# e-Tapperhandpiece19.net
KiCad netlist of a schematic drawn in EAGLE
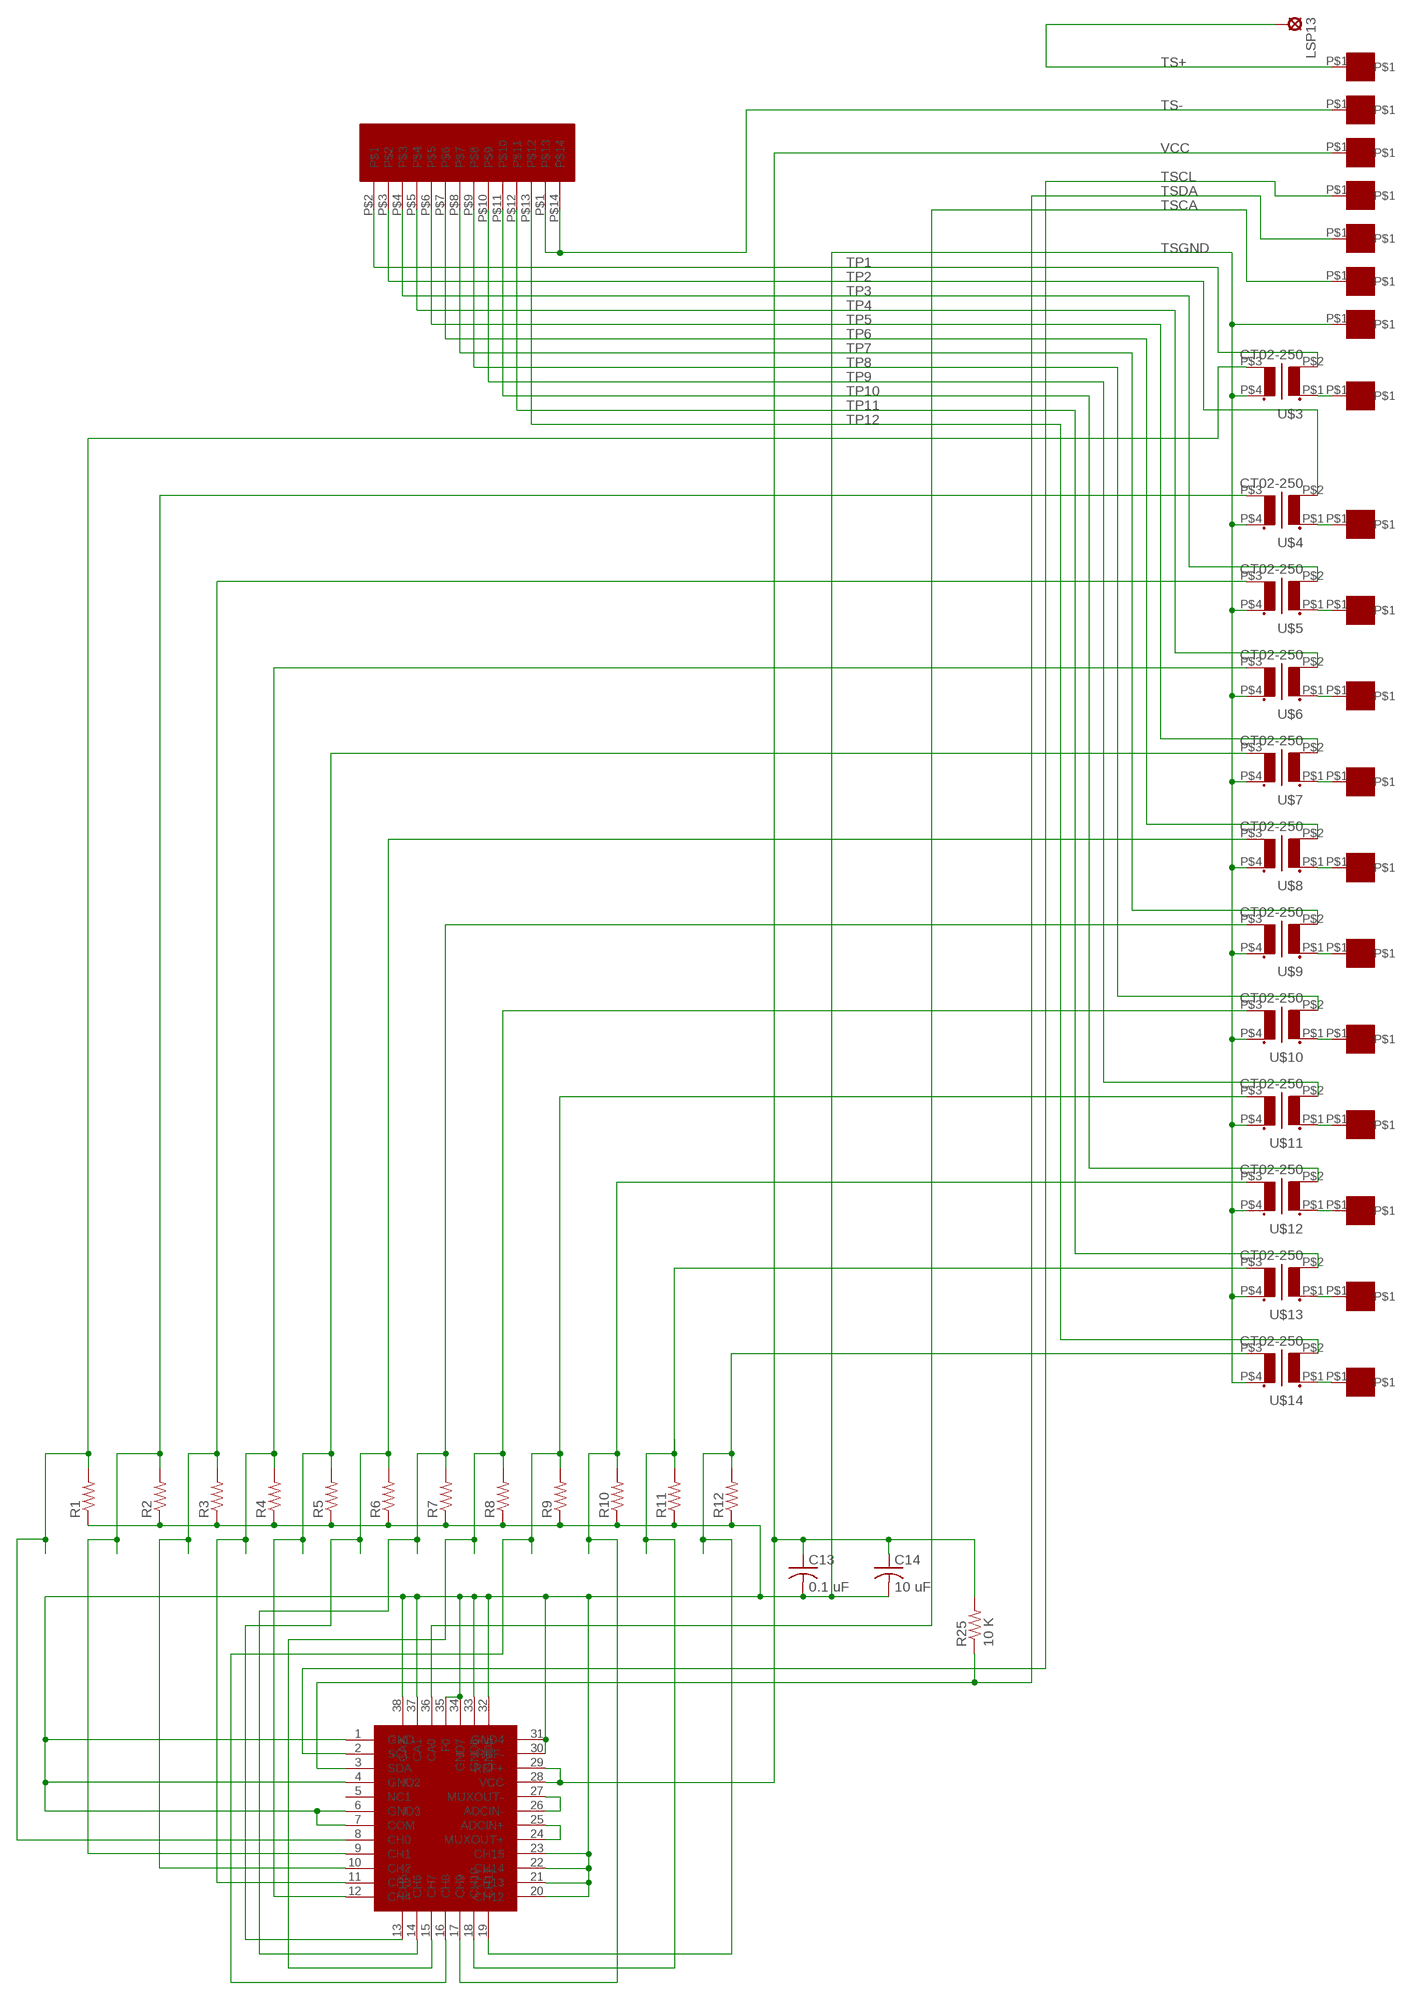
[diagram p0: schematic, sheet 1]

(export (version "E")
  (design (tool "Eeschema 10.0.6"))
  (components
    (comp (ref "C13")
      (value "0.1 uF")
      (footprint "eagle-import:C0603")
      (libsource (lib "eagle-import") (part "C-USC0603"))
    )
    (comp (ref "C14")
      (value "10 uF")
      (footprint "eagle-import:C0805")
      (libsource (lib "eagle-import") (part "C-USC0805"))
    )
    (comp (ref "LSP13")
      (value "SE11")
      (footprint "eagle-import:SE11")
      (libsource (lib "eagle-import") (part "SE11"))
    )
    (comp (ref "R1")
      (value "R-US_R0402")
      (footprint "eagle-import:R0402")
      (libsource (lib "eagle-import") (part "R-US_R0402"))
    )
    (comp (ref "R2")
      (value "R-US_R0402")
      (footprint "eagle-import:R0402")
      (libsource (lib "eagle-import") (part "R-US_R0402"))
    )
    (comp (ref "R3")
      (value "R-US_R0402")
      (footprint "eagle-import:R0402")
      (libsource (lib "eagle-import") (part "R-US_R0402"))
    )
    (comp (ref "R4")
      (value "R-US_R0402")
      (footprint "eagle-import:R0402")
      (libsource (lib "eagle-import") (part "R-US_R0402"))
    )
    (comp (ref "R5")
      (value "R-US_R0402")
      (footprint "eagle-import:R0402")
      (libsource (lib "eagle-import") (part "R-US_R0402"))
    )
    (comp (ref "R6")
      (value "R-US_R0402")
      (footprint "eagle-import:R0402")
      (libsource (lib "eagle-import") (part "R-US_R0402"))
    )
    (comp (ref "R7")
      (value "R-US_R0402")
      (footprint "eagle-import:R0402")
      (libsource (lib "eagle-import") (part "R-US_R0402"))
    )
    (comp (ref "R8")
      (value "R-US_R0402")
      (footprint "eagle-import:R0402")
      (libsource (lib "eagle-import") (part "R-US_R0402"))
    )
    (comp (ref "R9")
      (value "R-US_R0402")
      (footprint "eagle-import:R0402")
      (libsource (lib "eagle-import") (part "R-US_R0402"))
    )
    (comp (ref "R10")
      (value "R-US_R0402")
      (footprint "eagle-import:R0402")
      (libsource (lib "eagle-import") (part "R-US_R0402"))
    )
    (comp (ref "R11")
      (value "R-US_R0402")
      (footprint "eagle-import:R0402")
      (libsource (lib "eagle-import") (part "R-US_R0402"))
    )
    (comp (ref "R12")
      (value "R-US_R0402")
      (footprint "eagle-import:R0402")
      (libsource (lib "eagle-import") (part "R-US_R0402"))
    )
    (comp (ref "R25")
      (value "10 K")
      (footprint "eagle-import:R0402")
      (libsource (lib "eagle-import") (part "R-US_R0402"))
    )
    (comp (ref "TSP1")
      (value "ET1")
      (footprint "eagle-import:ET1")
      (libsource (lib "eagle-import") (part "ET1"))
    )
    (comp (ref "TSP2")
      (value "ET1")
      (footprint "eagle-import:ET1")
      (libsource (lib "eagle-import") (part "ET1"))
    )
    (comp (ref "TSP3")
      (value "ET1")
      (footprint "eagle-import:ET1")
      (libsource (lib "eagle-import") (part "ET1"))
    )
    (comp (ref "TSP4")
      (value "ET1")
      (footprint "eagle-import:ET1")
      (libsource (lib "eagle-import") (part "ET1"))
    )
    (comp (ref "TSP5")
      (value "ET1")
      (footprint "eagle-import:ET1")
      (libsource (lib "eagle-import") (part "ET1"))
    )
    (comp (ref "TSP6")
      (value "ET1")
      (footprint "eagle-import:ET1")
      (libsource (lib "eagle-import") (part "ET1"))
    )
    (comp (ref "TSP7")
      (value "ET1")
      (footprint "eagle-import:ET1")
      (libsource (lib "eagle-import") (part "ET1"))
    )
    (comp (ref "TSP8")
      (value "ET1")
      (footprint "eagle-import:ET1")
      (libsource (lib "eagle-import") (part "ET1"))
    )
    (comp (ref "TSP9")
      (value "ET1")
      (footprint "eagle-import:ET1")
      (libsource (lib "eagle-import") (part "ET1"))
    )
    (comp (ref "TSP10")
      (value "ET1")
      (footprint "eagle-import:ET1")
      (libsource (lib "eagle-import") (part "ET1"))
    )
    (comp (ref "TSP11")
      (value "ET1")
      (footprint "eagle-import:ET1")
      (libsource (lib "eagle-import") (part "ET1"))
    )
    (comp (ref "TSP12")
      (value "ET1")
      (footprint "eagle-import:ET1")
      (libsource (lib "eagle-import") (part "ET1"))
    )
    (comp (ref "TSP13")
      (value "ET1")
      (footprint "eagle-import:ET1")
      (libsource (lib "eagle-import") (part "ET1"))
    )
    (comp (ref "TSP14")
      (value "ET1")
      (footprint "eagle-import:ET1")
      (libsource (lib "eagle-import") (part "ET1"))
    )
    (comp (ref "TSP15")
      (value "ET1")
      (footprint "eagle-import:ET1")
      (libsource (lib "eagle-import") (part "ET1"))
    )
    (comp (ref "TSP16")
      (value "ET1")
      (footprint "eagle-import:ET1")
      (libsource (lib "eagle-import") (part "ET1"))
    )
    (comp (ref "TSP17")
      (value "ET1")
      (footprint "eagle-import:ET1")
      (libsource (lib "eagle-import") (part "ET1"))
    )
    (comp (ref "TSP18")
      (value "ET1")
      (footprint "eagle-import:ET1")
      (libsource (lib "eagle-import") (part "ET1"))
    )
    (comp (ref "TSP19")
      (value "ET1")
      (footprint "eagle-import:ET1")
      (libsource (lib "eagle-import") (part "ET1"))
    )
    (comp (ref "U$1")
      (value "LTC2497")
      (footprint "eagle-import:QFN38-5X7")
      (libsource (lib "eagle-import") (part "LTC2497"))
    )
    (comp (ref "U$2")
      (value "SS112D01")
      (footprint "eagle-import:SS112D01")
      (libsource (lib "eagle-import") (part "SS112D01"))
    )
    (comp (ref "U$3")
      (value "CT02-250")
      (footprint "eagle-import:CT02-250")
      (libsource (lib "eagle-import") (part "CT02-250"))
    )
    (comp (ref "U$4")
      (value "CT02-250")
      (footprint "eagle-import:CT02-250")
      (libsource (lib "eagle-import") (part "CT02-250"))
    )
    (comp (ref "U$5")
      (value "CT02-250")
      (footprint "eagle-import:CT02-250")
      (libsource (lib "eagle-import") (part "CT02-250"))
    )
    (comp (ref "U$6")
      (value "CT02-250")
      (footprint "eagle-import:CT02-250")
      (libsource (lib "eagle-import") (part "CT02-250"))
    )
    (comp (ref "U$7")
      (value "CT02-250")
      (footprint "eagle-import:CT02-250")
      (libsource (lib "eagle-import") (part "CT02-250"))
    )
    (comp (ref "U$8")
      (value "CT02-250")
      (footprint "eagle-import:CT02-250")
      (libsource (lib "eagle-import") (part "CT02-250"))
    )
    (comp (ref "U$9")
      (value "CT02-250")
      (footprint "eagle-import:CT02-250")
      (libsource (lib "eagle-import") (part "CT02-250"))
    )
    (comp (ref "U$10")
      (value "CT02-250")
      (footprint "eagle-import:CT02-250")
      (libsource (lib "eagle-import") (part "CT02-250"))
    )
    (comp (ref "U$11")
      (value "CT02-250")
      (footprint "eagle-import:CT02-250")
      (libsource (lib "eagle-import") (part "CT02-250"))
    )
    (comp (ref "U$12")
      (value "CT02-250")
      (footprint "eagle-import:CT02-250")
      (libsource (lib "eagle-import") (part "CT02-250"))
    )
    (comp (ref "U$13")
      (value "CT02-250")
      (footprint "eagle-import:CT02-250")
      (libsource (lib "eagle-import") (part "CT02-250"))
    )
    (comp (ref "U$14")
      (value "CT02-250")
      (footprint "eagle-import:CT02-250")
      (libsource (lib "eagle-import") (part "CT02-250"))
    )
  )
  (nets
    (net (code "1") (name "/TP1") (class "Default")
      (node (ref "U$2") (pin "P$2") (pinfunction "P$1_P$2") (pintype "bidirectional"))
      (node (ref "U$3") (pin "P$2") (pinfunction "P2_P$2") (pintype "passive"))
    )
    (net (code "2") (name "/TP2") (class "Default")
      (node (ref "U$2") (pin "P$3") (pinfunction "P$2_P$3") (pintype "bidirectional"))
      (node (ref "U$4") (pin "P$2") (pinfunction "P2_P$2") (pintype "passive"))
    )
    (net (code "3") (name "/TP3") (class "Default")
      (node (ref "U$2") (pin "P$4") (pinfunction "P$3_P$4") (pintype "bidirectional"))
      (node (ref "U$5") (pin "P$2") (pinfunction "P2_P$2") (pintype "passive"))
    )
    (net (code "4") (name "/TP4") (class "Default")
      (node (ref "U$2") (pin "P$5") (pinfunction "P$4_P$5") (pintype "bidirectional"))
      (node (ref "U$6") (pin "P$2") (pinfunction "P2_P$2") (pintype "passive"))
    )
    (net (code "5") (name "/TP5") (class "Default")
      (node (ref "U$2") (pin "P$6") (pinfunction "P$5_P$6") (pintype "bidirectional"))
      (node (ref "U$7") (pin "P$2") (pinfunction "P2_P$2") (pintype "passive"))
    )
    (net (code "6") (name "/TP6") (class "Default")
      (node (ref "U$2") (pin "P$7") (pinfunction "P$6_P$7") (pintype "bidirectional"))
      (node (ref "U$8") (pin "P$2") (pinfunction "P2_P$2") (pintype "passive"))
    )
    (net (code "7") (name "/TP7") (class "Default")
      (node (ref "U$2") (pin "P$8") (pinfunction "P$7_P$8") (pintype "bidirectional"))
      (node (ref "U$9") (pin "P$2") (pinfunction "P2_P$2") (pintype "passive"))
    )
    (net (code "8") (name "/TP8") (class "Default")
      (node (ref "U$10") (pin "P$2") (pinfunction "P2_P$2") (pintype "passive"))
      (node (ref "U$2") (pin "P$9") (pinfunction "P$8_P$9") (pintype "bidirectional"))
    )
    (net (code "9") (name "/TP9") (class "Default")
      (node (ref "U$11") (pin "P$2") (pinfunction "P2_P$2") (pintype "passive"))
      (node (ref "U$2") (pin "P$10") (pinfunction "P$9_P$10") (pintype "bidirectional"))
    )
    (net (code "10") (name "/TP10") (class "Default")
      (node (ref "U$12") (pin "P$2") (pinfunction "P2_P$2") (pintype "passive"))
      (node (ref "U$2") (pin "P$11") (pinfunction "P$10_P$11") (pintype "bidirectional"))
    )
    (net (code "11") (name "/TP11") (class "Default")
      (node (ref "U$13") (pin "P$2") (pinfunction "P2_P$2") (pintype "passive"))
      (node (ref "U$2") (pin "P$12") (pinfunction "P$11_P$12") (pintype "bidirectional"))
    )
    (net (code "12") (name "/TP12") (class "Default")
      (node (ref "U$14") (pin "P$2") (pinfunction "P2_P$2") (pintype "passive"))
      (node (ref "U$2") (pin "P$13") (pinfunction "P$12_P$13") (pintype "bidirectional"))
    )
    (net (code "13") (name "/TS+") (class "Default")
      (node (ref "LSP13") (pin "MP") (pinfunction "MP_MP") (pintype "passive"))
      (node (ref "TSP13") (pin "P$1") (pinfunction "P$1_P$1") (pintype "bidirectional"))
    )
    (net (code "14") (name "/TS-") (class "Default")
      (node (ref "TSP14") (pin "P$1") (pinfunction "P$1_P$1") (pintype "bidirectional"))
      (node (ref "U$2") (pin "P$1") (pinfunction "P$13_P$1") (pintype "bidirectional"))
      (node (ref "U$2") (pin "P$14") (pinfunction "P$14_P$14") (pintype "bidirectional"))
    )
    (net (code "15") (name "/TSCA") (class "Default")
      (node (ref "TSP18") (pin "P$1") (pinfunction "P$1_P$1") (pintype "bidirectional"))
      (node (ref "U$1") (pin "36") (pinfunction "CA0_36") (pintype "bidirectional"))
    )
    (net (code "16") (name "/TSCL") (class "Default")
      (node (ref "TSP16") (pin "P$1") (pinfunction "P$1_P$1") (pintype "bidirectional"))
      (node (ref "U$1") (pin "2") (pinfunction "SCL_2") (pintype "bidirectional"))
    )
    (net (code "17") (name "/TSDA") (class "Default")
      (node (ref "R25") (pin "1") (pinfunction "1_1") (pintype "passive"))
      (node (ref "TSP17") (pin "P$1") (pinfunction "P$1_P$1") (pintype "bidirectional"))
      (node (ref "U$1") (pin "3") (pinfunction "SDA_3") (pintype "bidirectional"))
    )
    (net (code "18") (name "/TSGND") (class "Default")
      (node (ref "C13") (pin "2") (pinfunction "2_2") (pintype "passive"))
      (node (ref "C14") (pin "2") (pinfunction "2_2") (pintype "passive"))
      (node (ref "R1") (pin "1") (pinfunction "1_1") (pintype "passive"))
      (node (ref "R10") (pin "1") (pinfunction "1_1") (pintype "passive"))
      (node (ref "R11") (pin "1") (pinfunction "1_1") (pintype "passive"))
      (node (ref "R12") (pin "1") (pinfunction "1_1") (pintype "passive"))
      (node (ref "R2") (pin "1") (pinfunction "1_1") (pintype "passive"))
      (node (ref "R3") (pin "1") (pinfunction "1_1") (pintype "passive"))
      (node (ref "R4") (pin "1") (pinfunction "1_1") (pintype "passive"))
      (node (ref "R5") (pin "1") (pinfunction "1_1") (pintype "passive"))
      (node (ref "R6") (pin "1") (pinfunction "1_1") (pintype "passive"))
      (node (ref "R7") (pin "1") (pinfunction "1_1") (pintype "passive"))
      (node (ref "R8") (pin "1") (pinfunction "1_1") (pintype "passive"))
      (node (ref "R9") (pin "1") (pinfunction "1_1") (pintype "passive"))
      (node (ref "TSP19") (pin "P$1") (pinfunction "P$1_P$1") (pintype "bidirectional"))
      (node (ref "U$1") (pin "1") (pinfunction "GND_1") (pintype "power_in"))
      (node (ref "U$1") (pin "20") (pinfunction "CH12_20") (pintype "input"))
      (node (ref "U$1") (pin "21") (pinfunction "CH13_21") (pintype "input"))
      (node (ref "U$1") (pin "22") (pinfunction "CH14_22") (pintype "input"))
      (node (ref "U$1") (pin "23") (pinfunction "CH15_23") (pintype "input"))
      (node (ref "U$1") (pin "30") (pinfunction "REF-_30") (pintype "bidirectional"))
      (node (ref "U$1") (pin "31") (pinfunction "GND4_31") (pintype "power_in"))
      (node (ref "U$1") (pin "32") (pinfunction "GND5_32") (pintype "power_in"))
      (node (ref "U$1") (pin "33") (pinfunction "GND6_33") (pintype "power_in"))
      (node (ref "U$1") (pin "34") (pinfunction "GND7_34") (pintype "power_in"))
      (node (ref "U$1") (pin "35") (pinfunction "F0_35") (pintype "bidirectional"))
      (node (ref "U$1") (pin "37") (pinfunction "CA1_37") (pintype "bidirectional"))
      (node (ref "U$1") (pin "38") (pinfunction "CA2_38") (pintype "bidirectional"))
      (node (ref "U$1") (pin "4") (pinfunction "GND2_4") (pintype "power_in"))
      (node (ref "U$1") (pin "6") (pinfunction "GND3_6") (pintype "power_in"))
      (node (ref "U$1") (pin "7") (pinfunction "COM_7") (pintype "power_in"))
      (node (ref "U$10") (pin "P$4") (pinfunction "S1_P$4") (pintype "passive"))
      (node (ref "U$11") (pin "P$4") (pinfunction "S1_P$4") (pintype "passive"))
      (node (ref "U$12") (pin "P$4") (pinfunction "S1_P$4") (pintype "passive"))
      (node (ref "U$13") (pin "P$4") (pinfunction "S1_P$4") (pintype "passive"))
      (node (ref "U$14") (pin "P$4") (pinfunction "S1_P$4") (pintype "passive"))
      (node (ref "U$3") (pin "P$4") (pinfunction "S1_P$4") (pintype "passive"))
      (node (ref "U$4") (pin "P$4") (pinfunction "S1_P$4") (pintype "passive"))
      (node (ref "U$5") (pin "P$4") (pinfunction "S1_P$4") (pintype "passive"))
      (node (ref "U$6") (pin "P$4") (pinfunction "S1_P$4") (pintype "passive"))
      (node (ref "U$7") (pin "P$4") (pinfunction "S1_P$4") (pintype "passive"))
      (node (ref "U$8") (pin "P$4") (pinfunction "S1_P$4") (pintype "passive"))
      (node (ref "U$9") (pin "P$4") (pinfunction "S1_P$4") (pintype "passive"))
    )
    (net (code "19") (name "/VCC") (class "Default")
      (node (ref "C13") (pin "1") (pinfunction "1_1") (pintype "passive"))
      (node (ref "C14") (pin "1") (pinfunction "1_1") (pintype "passive"))
      (node (ref "R25") (pin "2") (pinfunction "2_2") (pintype "passive"))
      (node (ref "TSP15") (pin "P$1") (pinfunction "P$1_P$1") (pintype "bidirectional"))
      (node (ref "U$1") (pin "28") (pinfunction "VCC_28") (pintype "power_in"))
      (node (ref "U$1") (pin "29") (pinfunction "REF+_29") (pintype "bidirectional"))
    )
    (net (code "20") (name "Net-(U$1-ADCIN+)") (class "Default")
      (node (ref "U$1") (pin "24") (pinfunction "MUXOUT+_24") (pintype "bidirectional"))
      (node (ref "U$1") (pin "25") (pinfunction "ADCIN+_25") (pintype "bidirectional"))
    )
    (net (code "21") (name "Net-(U$1-ADCIN-)") (class "Default")
      (node (ref "U$1") (pin "26") (pinfunction "ADCIN-_26") (pintype "bidirectional"))
      (node (ref "U$1") (pin "27") (pinfunction "MUXOUT-_27") (pintype "bidirectional"))
    )
    (net (code "22") (name "Net-(U$1-CH0)") (class "Default")
      (node (ref "R1") (pin "2") (pinfunction "2_2") (pintype "passive"))
      (node (ref "U$1") (pin "8") (pinfunction "CH0_8") (pintype "input"))
      (node (ref "U$3") (pin "P$3") (pinfunction "S2_P$3") (pintype "passive"))
    )
    (net (code "23") (name "Net-(U$1-CH1)") (class "Default")
      (node (ref "R2") (pin "2") (pinfunction "2_2") (pintype "passive"))
      (node (ref "U$1") (pin "9") (pinfunction "CH1_9") (pintype "input"))
      (node (ref "U$4") (pin "P$3") (pinfunction "S2_P$3") (pintype "passive"))
    )
    (net (code "24") (name "Net-(U$1-CH2)") (class "Default")
      (node (ref "R3") (pin "2") (pinfunction "2_2") (pintype "passive"))
      (node (ref "U$1") (pin "10") (pinfunction "CH2_10") (pintype "input"))
      (node (ref "U$5") (pin "P$3") (pinfunction "S2_P$3") (pintype "passive"))
    )
    (net (code "25") (name "Net-(U$1-CH3)") (class "Default")
      (node (ref "R4") (pin "2") (pinfunction "2_2") (pintype "passive"))
      (node (ref "U$1") (pin "11") (pinfunction "CH3_11") (pintype "input"))
      (node (ref "U$6") (pin "P$3") (pinfunction "S2_P$3") (pintype "passive"))
    )
    (net (code "26") (name "Net-(U$1-CH4)") (class "Default")
      (node (ref "R5") (pin "2") (pinfunction "2_2") (pintype "passive"))
      (node (ref "U$1") (pin "12") (pinfunction "CH4_12") (pintype "input"))
      (node (ref "U$7") (pin "P$3") (pinfunction "S2_P$3") (pintype "passive"))
    )
    (net (code "27") (name "Net-(U$1-CH5)") (class "Default")
      (node (ref "R6") (pin "2") (pinfunction "2_2") (pintype "passive"))
      (node (ref "U$1") (pin "13") (pinfunction "CH5_13") (pintype "input"))
      (node (ref "U$8") (pin "P$3") (pinfunction "S2_P$3") (pintype "passive"))
    )
    (net (code "28") (name "Net-(U$1-CH6)") (class "Default")
      (node (ref "R7") (pin "2") (pinfunction "2_2") (pintype "passive"))
      (node (ref "U$1") (pin "14") (pinfunction "CH6_14") (pintype "input"))
      (node (ref "U$9") (pin "P$3") (pinfunction "S2_P$3") (pintype "passive"))
    )
    (net (code "29") (name "Net-(U$1-CH7)") (class "Default")
      (node (ref "R8") (pin "2") (pinfunction "2_2") (pintype "passive"))
      (node (ref "U$1") (pin "15") (pinfunction "CH7_15") (pintype "input"))
      (node (ref "U$10") (pin "P$3") (pinfunction "S2_P$3") (pintype "passive"))
    )
    (net (code "30") (name "Net-(U$1-CH8)") (class "Default")
      (node (ref "R9") (pin "2") (pinfunction "2_2") (pintype "passive"))
      (node (ref "U$1") (pin "16") (pinfunction "CH8_16") (pintype "input"))
      (node (ref "U$11") (pin "P$3") (pinfunction "S2_P$3") (pintype "passive"))
    )
    (net (code "31") (name "Net-(U$1-CH9)") (class "Default")
      (node (ref "R10") (pin "2") (pinfunction "2_2") (pintype "passive"))
      (node (ref "U$1") (pin "17") (pinfunction "CH9_17") (pintype "input"))
      (node (ref "U$12") (pin "P$3") (pinfunction "S2_P$3") (pintype "passive"))
    )
    (net (code "32") (name "Net-(U$1-CH10)") (class "Default")
      (node (ref "R11") (pin "2") (pinfunction "2_2") (pintype "passive"))
      (node (ref "U$1") (pin "18") (pinfunction "CH10_18") (pintype "input"))
      (node (ref "U$13") (pin "P$3") (pinfunction "S2_P$3") (pintype "passive"))
    )
    (net (code "33") (name "Net-(U$1-CH11)") (class "Default")
      (node (ref "R12") (pin "2") (pinfunction "2_2") (pintype "passive"))
      (node (ref "U$1") (pin "19") (pinfunction "CH11_19") (pintype "input"))
      (node (ref "U$14") (pin "P$3") (pinfunction "S2_P$3") (pintype "passive"))
    )
    (net (code "34") (name "Net-(U$3-P1)") (class "Default")
      (node (ref "TSP1") (pin "P$1") (pinfunction "P$1_P$1") (pintype "bidirectional"))
      (node (ref "U$3") (pin "P$1") (pinfunction "P1_P$1") (pintype "passive"))
    )
    (net (code "35") (name "Net-(U$4-P1)") (class "Default")
      (node (ref "TSP2") (pin "P$1") (pinfunction "P$1_P$1") (pintype "bidirectional"))
      (node (ref "U$4") (pin "P$1") (pinfunction "P1_P$1") (pintype "passive"))
    )
    (net (code "36") (name "Net-(U$5-P1)") (class "Default")
      (node (ref "TSP3") (pin "P$1") (pinfunction "P$1_P$1") (pintype "bidirectional"))
      (node (ref "U$5") (pin "P$1") (pinfunction "P1_P$1") (pintype "passive"))
    )
    (net (code "37") (name "Net-(U$6-P1)") (class "Default")
      (node (ref "TSP4") (pin "P$1") (pinfunction "P$1_P$1") (pintype "bidirectional"))
      (node (ref "U$6") (pin "P$1") (pinfunction "P1_P$1") (pintype "passive"))
    )
    (net (code "38") (name "Net-(U$7-P1)") (class "Default")
      (node (ref "TSP5") (pin "P$1") (pinfunction "P$1_P$1") (pintype "bidirectional"))
      (node (ref "U$7") (pin "P$1") (pinfunction "P1_P$1") (pintype "passive"))
    )
    (net (code "39") (name "Net-(U$8-P1)") (class "Default")
      (node (ref "TSP6") (pin "P$1") (pinfunction "P$1_P$1") (pintype "bidirectional"))
      (node (ref "U$8") (pin "P$1") (pinfunction "P1_P$1") (pintype "passive"))
    )
    (net (code "40") (name "Net-(U$9-P1)") (class "Default")
      (node (ref "TSP7") (pin "P$1") (pinfunction "P$1_P$1") (pintype "bidirectional"))
      (node (ref "U$9") (pin "P$1") (pinfunction "P1_P$1") (pintype "passive"))
    )
    (net (code "41") (name "Net-(U$10-P1)") (class "Default")
      (node (ref "TSP8") (pin "P$1") (pinfunction "P$1_P$1") (pintype "bidirectional"))
      (node (ref "U$10") (pin "P$1") (pinfunction "P1_P$1") (pintype "passive"))
    )
    (net (code "42") (name "Net-(U$11-P1)") (class "Default")
      (node (ref "TSP9") (pin "P$1") (pinfunction "P$1_P$1") (pintype "bidirectional"))
      (node (ref "U$11") (pin "P$1") (pinfunction "P1_P$1") (pintype "passive"))
    )
    (net (code "43") (name "Net-(U$12-P1)") (class "Default")
      (node (ref "TSP10") (pin "P$1") (pinfunction "P$1_P$1") (pintype "bidirectional"))
      (node (ref "U$12") (pin "P$1") (pinfunction "P1_P$1") (pintype "passive"))
    )
    (net (code "44") (name "Net-(U$13-P1)") (class "Default")
      (node (ref "TSP11") (pin "P$1") (pinfunction "P$1_P$1") (pintype "bidirectional"))
      (node (ref "U$13") (pin "P$1") (pinfunction "P1_P$1") (pintype "passive"))
    )
    (net (code "45") (name "Net-(U$14-P1)") (class "Default")
      (node (ref "TSP12") (pin "P$1") (pinfunction "P$1_P$1") (pintype "bidirectional"))
      (node (ref "U$14") (pin "P$1") (pinfunction "P1_P$1") (pintype "passive"))
    )
    (net (code "46") (name "unconnected-(U$1-NC1-Pad5)") (class "Default")
      (node (ref "U$1") (pin "5") (pinfunction "NC1_5") (pintype "no_connect"))
    )
  )
)
